# USB_to_SATA_bridge.net
KiCad netlist of a schematic drawn in Altium Designer
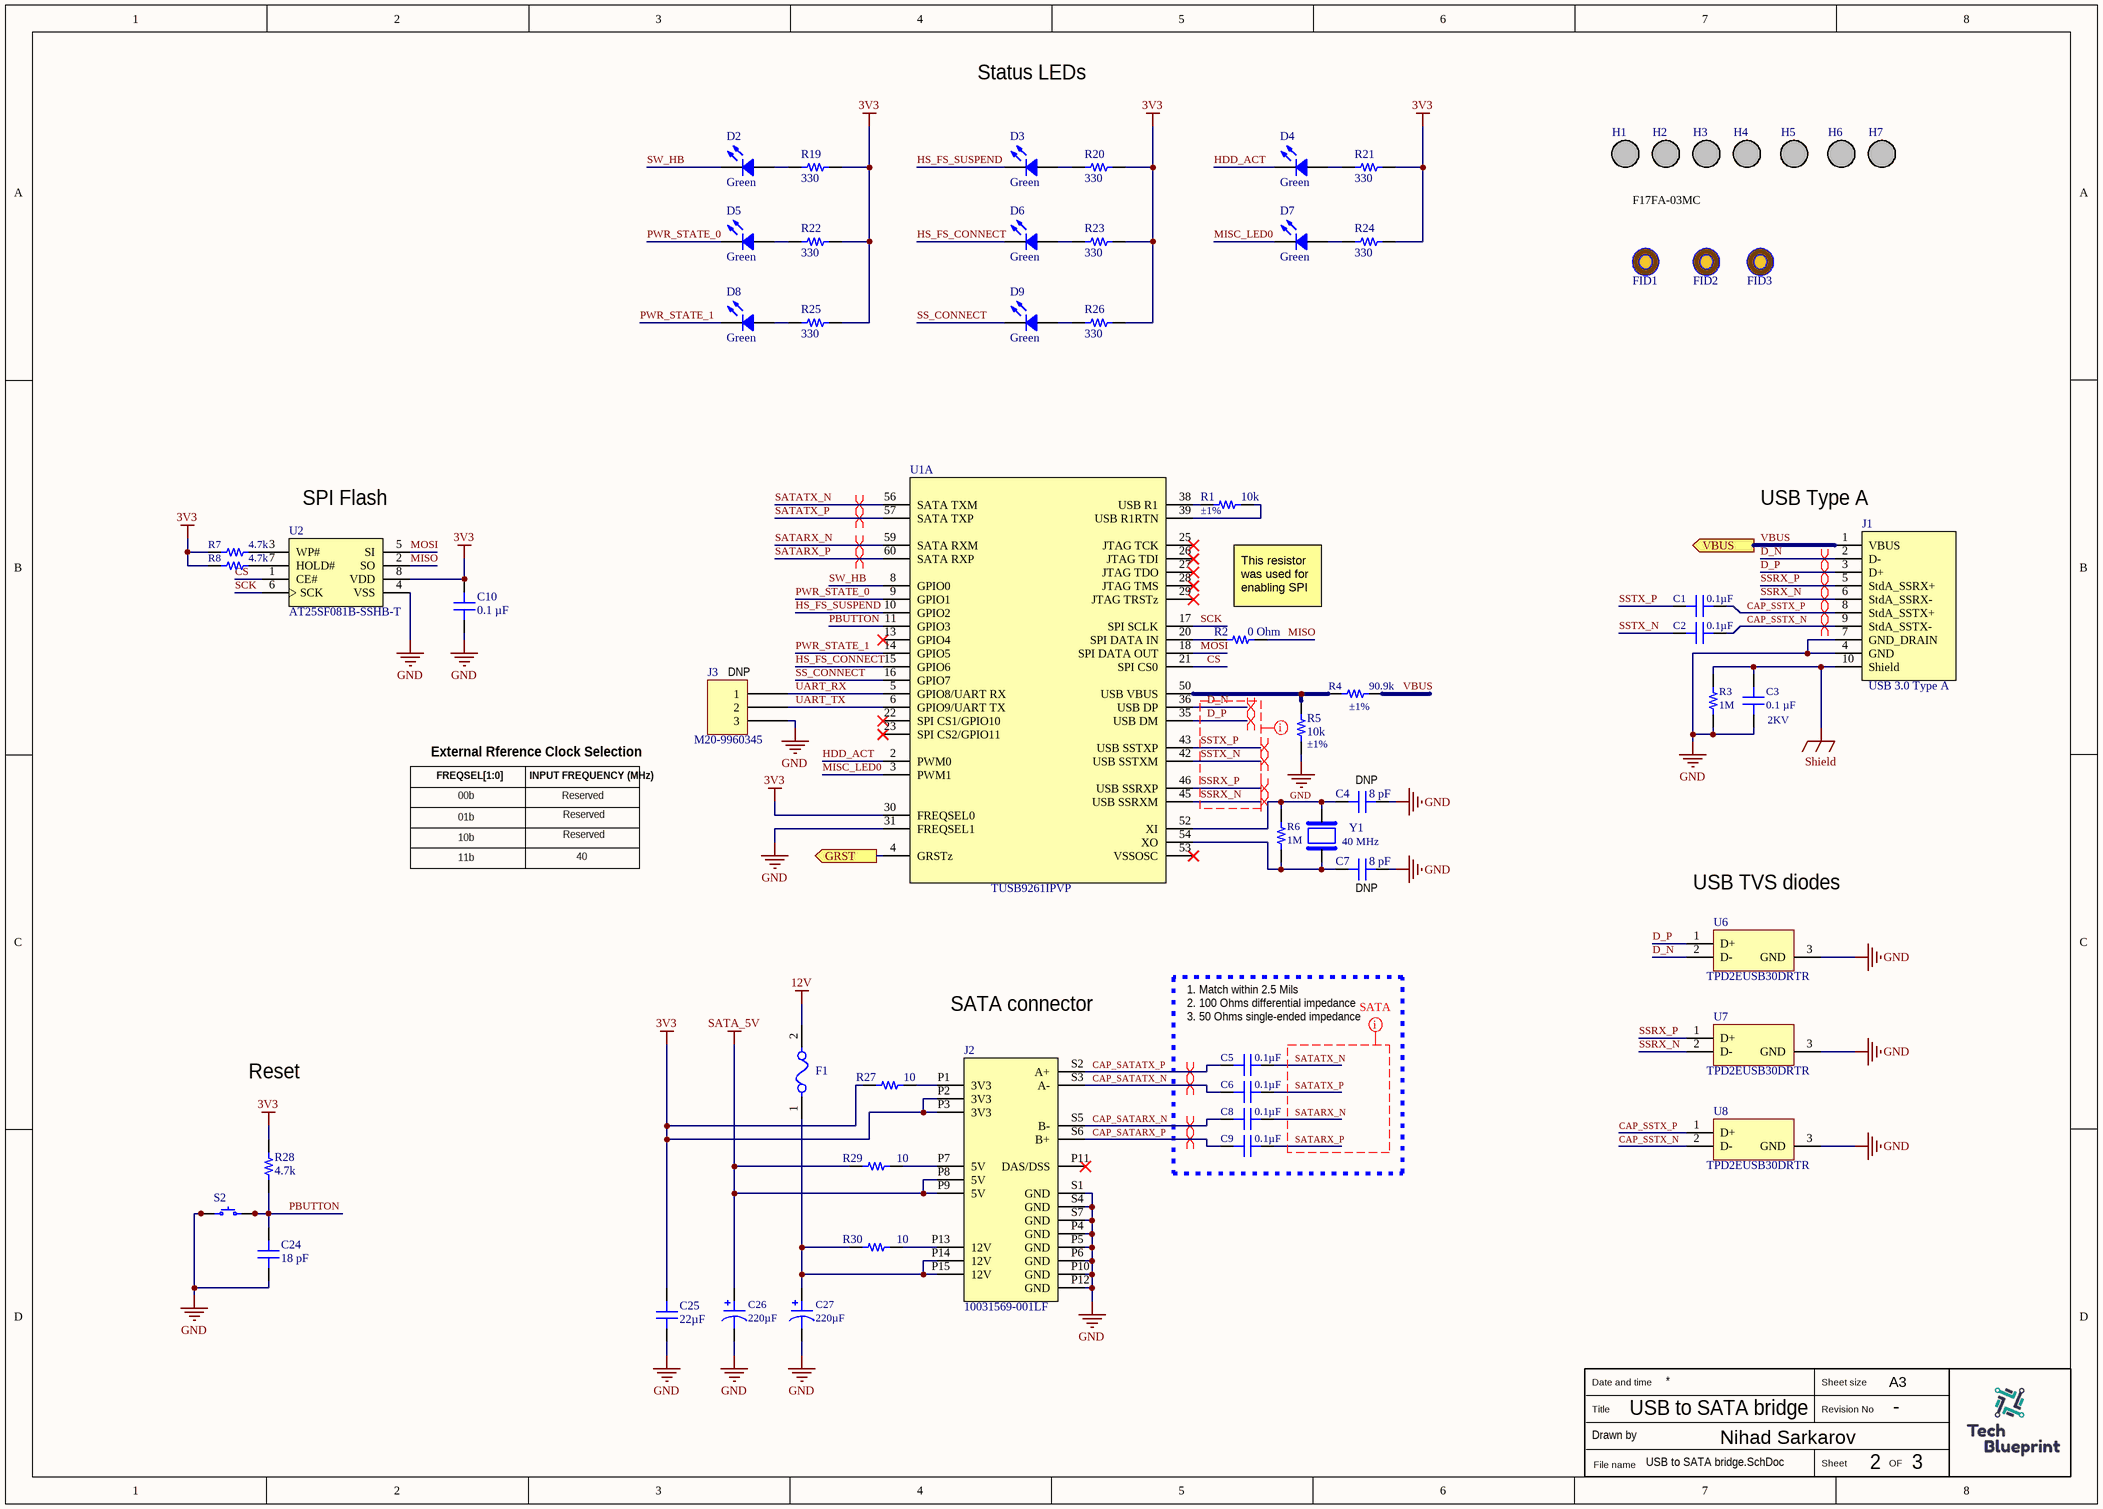
[diagram p0: USB to SATA bridge.SchDoc]

(export (version "E")
  (design (tool "Eeschema 10.0.6"))
  (components
    (comp (ref "C1")
      (value "0.1µF")
      (footprint "CAP 0402_1005")
      (description "CAP CER 0.1UF 16V X7R 0402")
      (fields
        (field (name "PART NUMBER") "0402YC104JAT4A")
        (field (name "CAPACITANCE") "0.1µF")
        (field (name "MANUFACTURER") "AVX Corporation")
      )
      (libsource (lib "Celestial Altium Library - altium_library") (part "Capacitor"))
    )
    (comp (ref "C2")
      (value "0.1µF")
      (footprint "CAP 0402_1005")
      (description "CAP CER 0.1UF 16V X7R 0402")
      (fields
        (field (name "PART NUMBER") "0402YC104JAT4A")
        (field (name "CAPACITANCE") "0.1µF")
        (field (name "MANUFACTURER") "AVX Corporation")
      )
      (libsource (lib "Celestial Altium Library - altium_library") (part "Capacitor"))
    )
    (comp (ref "C3")
      (value "0.1 µF")
      (footprint "MURATA GRM155 0402_1005")
      (description "CAP CER 0.1UF 100V X5R 0402")
      (fields
        (field (name "PART NUMBER") "GRM155R62A104ME14D")
        (field (name "CAPACITANCE") "0.1 µF")
        (field (name "MANUFACTURER") "Murata Electronics")
        (field (name "VOLTAGE - RATED") "2KV")
      )
      (libsource (lib "Celestial Altium Library - altium_library") (part "Capacitor"))
    )
    (comp (ref "C4")
      (value "8 pF")
      (footprint "MURATA GCM155 0402_1005")
      (description "CAP CER 8PF 50V C0G/NP0 0402")
      (fields
        (field (name "PART NUMBER") "GCM1555C1H8R0DA16D")
        (field (name "CAPACITANCE") "8 pF")
        (field (name "MANUFACTURER") "Murata Electronics")
      )
      (libsource (lib "Celestial Altium Library - altium_library") (part "Capacitor"))
    )
    (comp (ref "C5")
      (value "0.1µF")
      (footprint "CAP 0402_1005")
      (description "CAP CER 0.1UF 16V X7R 0402")
      (fields
        (field (name "PART NUMBER") "0402YC104JAT4A")
        (field (name "CAPACITANCE") "0.1µF")
        (field (name "MANUFACTURER") "AVX Corporation")
      )
      (libsource (lib "Celestial Altium Library - altium_library") (part "Capacitor"))
    )
    (comp (ref "C6")
      (value "0.1µF")
      (footprint "CAP 0402_1005")
      (description "CAP CER 0.1UF 16V X7R 0402")
      (fields
        (field (name "PART NUMBER") "0402YC104JAT4A")
        (field (name "CAPACITANCE") "0.1µF")
        (field (name "MANUFACTURER") "AVX Corporation")
      )
      (libsource (lib "Celestial Altium Library - altium_library") (part "Capacitor"))
    )
    (comp (ref "C7")
      (value "8 pF")
      (footprint "MURATA GCM155 0402_1005")
      (description "CAP CER 8PF 50V C0G/NP0 0402")
      (fields
        (field (name "PART NUMBER") "GCM1555C1H8R0DA16D")
        (field (name "CAPACITANCE") "8 pF")
        (field (name "MANUFACTURER") "Murata Electronics")
      )
      (libsource (lib "Celestial Altium Library - altium_library") (part "Capacitor"))
    )
    (comp (ref "C8")
      (value "0.1µF")
      (footprint "CAP 0402_1005")
      (description "CAP CER 0.1UF 16V X7R 0402")
      (fields
        (field (name "PART NUMBER") "0402YC104JAT4A")
        (field (name "CAPACITANCE") "0.1µF")
        (field (name "MANUFACTURER") "AVX Corporation")
      )
      (libsource (lib "Celestial Altium Library - altium_library") (part "Capacitor"))
    )
    (comp (ref "C9")
      (value "0.1µF")
      (footprint "CAP 0402_1005")
      (description "CAP CER 0.1UF 16V X7R 0402")
      (fields
        (field (name "PART NUMBER") "0402YC104JAT4A")
        (field (name "CAPACITANCE") "0.1µF")
        (field (name "MANUFACTURER") "AVX Corporation")
      )
      (libsource (lib "Celestial Altium Library - altium_library") (part "Capacitor"))
    )
    (comp (ref "C10")
      (value "0.1 µF")
      (footprint "CAP 0603_1608")
      (description "CAP CER 0.1UF 50V X7R 0603")
      (fields
        (field (name "PART NUMBER") "CL10B104KB85PND")
        (field (name "CAPACITANCE") "0.1 µF")
        (field (name "MANUFACTURER") "Samsung Electro-Mechanics")
      )
      (libsource (lib "Celestial Altium Library - altium_library") (part "Capacitor"))
    )
    (comp (ref "C24")
      (value "18 pF")
      (footprint "CAP 0402_1005")
      (description "CAP CER 18PF 50V C0G 0402")
      (fields
        (field (name "PART NUMBER") "CGA2B2C0G1H180J050BA")
        (field (name "CAPACITANCE") "18 pF")
        (field (name "MANUFACTURER") "TDK Corporation")
      )
      (libsource (lib "Celestial Altium Library - altium_library") (part "Capacitor"))
    )
    (comp (ref "C25")
      (value "22µF")
      (footprint "CAP 1206_3216 - 1.8MM")
      (description "CAP CER 22UF 16V X5R 1206")
      (fields
        (field (name "PART NUMBER") "1206YD226KAT2A")
        (field (name "CAPACITANCE") "22µF")
        (field (name "MANUFACTURER") "AVX Corporation")
      )
      (libsource (lib "Celestial Altium Library - altium_library") (part "Capacitor"))
    )
    (comp (ref "C26")
      (value "220µF")
      (footprint "CAP ALSMD 8.3MM H10.5MM")
      (description "CAP ALUM 220UF 20% 25V SMD")
      (fields (field (name "PART NUMBER") "UUR1E221MNL6GS") (field (name "MANUFACTURER") "Nichicon"))
      (libsource (lib "Celestial Altium Library - altium_library") (part "Polarised Capacitor"))
    )
    (comp (ref "C27")
      (value "220µF")
      (footprint "CAP ALSMD 8.3MM H10.5MM")
      (description "CAP ALUM 220UF 20% 25V SMD")
      (fields (field (name "PART NUMBER") "UUR1E221MNL6GS") (field (name "MANUFACTURER") "Nichicon"))
      (libsource (lib "Celestial Altium Library - altium_library") (part "Polarised Capacitor"))
    )
    (comp (ref "D2")
      (value "Green")
      (footprint "LED 0805_2012 GREEN")
      (description "0805 LED RED 570NM DOMINANT, 565")
      (fields
        (field (name "PART NUMBER") "QBLP631-YG1-2943")
        (field (name "MANUFACTURER") "QT Brightek (QTB)")
      )
      (libsource (lib "Celestial Altium Library - altium_library") (part "LED"))
    )
    (comp (ref "D3")
      (value "Green")
      (footprint "LED 0805_2012 GREEN")
      (description "0805 LED RED 570NM DOMINANT, 565")
      (fields
        (field (name "PART NUMBER") "QBLP631-YG1-2943")
        (field (name "MANUFACTURER") "QT Brightek (QTB)")
      )
      (libsource (lib "Celestial Altium Library - altium_library") (part "LED"))
    )
    (comp (ref "D4")
      (value "Green")
      (footprint "LED 0805_2012 GREEN")
      (description "0805 LED RED 570NM DOMINANT, 565")
      (fields
        (field (name "PART NUMBER") "QBLP631-YG1-2943")
        (field (name "MANUFACTURER") "QT Brightek (QTB)")
      )
      (libsource (lib "Celestial Altium Library - altium_library") (part "LED"))
    )
    (comp (ref "D5")
      (value "Green")
      (footprint "LED 0805_2012 GREEN")
      (description "0805 LED RED 570NM DOMINANT, 565")
      (fields
        (field (name "PART NUMBER") "QBLP631-YG1-2943")
        (field (name "MANUFACTURER") "QT Brightek (QTB)")
      )
      (libsource (lib "Celestial Altium Library - altium_library") (part "LED"))
    )
    (comp (ref "D6")
      (value "Green")
      (footprint "LED 0805_2012 GREEN")
      (description "0805 LED RED 570NM DOMINANT, 565")
      (fields
        (field (name "PART NUMBER") "QBLP631-YG1-2943")
        (field (name "MANUFACTURER") "QT Brightek (QTB)")
      )
      (libsource (lib "Celestial Altium Library - altium_library") (part "LED"))
    )
    (comp (ref "D7")
      (value "Green")
      (footprint "LED 0805_2012 GREEN")
      (description "0805 LED RED 570NM DOMINANT, 565")
      (fields
        (field (name "PART NUMBER") "QBLP631-YG1-2943")
        (field (name "MANUFACTURER") "QT Brightek (QTB)")
      )
      (libsource (lib "Celestial Altium Library - altium_library") (part "LED"))
    )
    (comp (ref "D8")
      (value "Green")
      (footprint "LED 0805_2012 GREEN")
      (description "0805 LED RED 570NM DOMINANT, 565")
      (fields
        (field (name "PART NUMBER") "QBLP631-YG1-2943")
        (field (name "MANUFACTURER") "QT Brightek (QTB)")
      )
      (libsource (lib "Celestial Altium Library - altium_library") (part "LED"))
    )
    (comp (ref "D9")
      (value "Green")
      (footprint "LED 0805_2012 GREEN")
      (description "0805 LED RED 570NM DOMINANT, 565")
      (fields
        (field (name "PART NUMBER") "QBLP631-YG1-2943")
        (field (name "MANUFACTURER") "QT Brightek (QTB)")
      )
      (libsource (lib "Celestial Altium Library - altium_library") (part "LED"))
    )
    (comp (ref "F1")
      (value "MINISMDC150F/24-2")
      (footprint "FP-MINISMDC150F-MFG")
      (description "PTC RESET FUSE 24V 1.5A 1812")
      (fields
        (field (name "MANUFACTURER") "Littelfuse")
        (field (name "OCTOPART") "https://octopart.com/minismdc150f%2F24-2-littelfuse-74215024")
      )
      (libsource (lib "Altium Content Vault") (part "5bcf9b9f640e542cf0359d10258e979"))
    )
    (comp (ref "FID1")
      (value "FID_040")
      (footprint "FID_040")
      (description "Fiducial with various available footprints")
      (libsource (lib "nRF52-Intro") (part "FIDUCIAL"))
    )
    (comp (ref "FID2")
      (value "FID_040")
      (footprint "FID_040")
      (description "Fiducial with various available footprints")
      (libsource (lib "nRF52-Intro") (part "FIDUCIAL"))
    )
    (comp (ref "FID3")
      (value "FID_040")
      (footprint "FID_040")
      (description "Fiducial with various available footprints")
      (libsource (lib "nRF52-Intro") (part "FIDUCIAL"))
    )
    (comp (ref "H1") (value "Hole") (footprint "Hole") (libsource (lib "USB to SATA") (part "Hole")))
    (comp (ref "H2") (value "Hole") (footprint "Hole") (libsource (lib "USB to SATA") (part "Hole")))
    (comp (ref "H3") (value "Hole") (footprint "Hole") (libsource (lib "USB to SATA") (part "Hole")))
    (comp (ref "H4")
      (value "Mounting hole")
      (footprint "Mounting hole")
      (libsource (lib "USB to SATA") (part "Mounting hole"))
    )
    (comp (ref "H5")
      (value "Mounting hole")
      (footprint "Mounting hole")
      (libsource (lib "USB to SATA") (part "Mounting hole"))
    )
    (comp (ref "H6")
      (value "Mounting hole")
      (footprint "Mounting hole")
      (libsource (lib "USB to SATA") (part "Mounting hole"))
    )
    (comp (ref "H7")
      (value "Mounting hole")
      (footprint "Mounting hole")
      (libsource (lib "USB to SATA") (part "Mounting hole"))
    )
    (comp (ref "J1")
      (value "USB 3.0 Type A")
      (footprint "USB 3.0 Type A")
      (description "USB 3.0 Type A male connector")
      (libsource (lib "USB to SATA") (part "USB 3.0 Type A"))
    )
    (comp (ref "J2")
      (value "10031569-001LF")
      (footprint "AMPHENOL_10031569-001LF")
      (fields (field (name "MF") "{'manufacturer': u'Amphenol ICC'}"))
      (libsource (lib "USB to SATA") (part "10031569-001LF"))
    )
    (comp (ref "J3")
      (value "M20-9960345")
      (footprint "HARWIN M20-9960345")
      (description "CONN HEADER R/A 3POS 2.54MM")
      (fields (field (name "MANUFACTURER") "Harwin Inc."))
      (libsource (lib "Celestial Altium Library - altium_library") (part "3 Pin"))
    )
    (comp (ref "R1")
      (value "10k")
      (footprint "YAGEO RES 0402_1005")
      (description "RES 10K OHM 1% 1/5W 0402")
      (fields
        (field (name "PART NUMBER") "SR0402FR-7T10KL")
        (field (name "MANUFACTURER") "Yageo")
        (field (name "TOLERANCE") "±1%")
      )
      (libsource (lib "Celestial Altium Library - altium_library") (part "Resistor"))
    )
    (comp (ref "R2")
      (value "0 Ohm")
      (footprint "RES 0603_1608")
      (description "RCS0603 0R0 ET6 E3")
      (fields (field (name "PART NUMBER") "RCS06030000Z0EC") (field (name "MANUFACTURER") "Vishay Dale"))
      (libsource (lib "Celestial Altium Library - altium_library") (part "Resistor"))
    )
    (comp (ref "R3")
      (value "1M")
      (footprint "RES 0603_1608")
      (description "RES 1M OHM 5% 1/10W 0603")
      (fields
        (field (name "PART NUMBER") "RMCF0603JT1M00")
        (field (name "MANUFACTURER") "Stackpole Electronics Inc")
      )
      (libsource (lib "Celestial Altium Library - altium_library") (part "Resistor"))
    )
    (comp (ref "R4")
      (value "90.9k")
      (footprint "RES 0603_1608")
      (description "RES SMD 90.9K OHM 1% 1/8W 0603")
      (fields
        (field (name "PART NUMBER") "MCT06030C9092FP500")
        (field (name "MANUFACTURER") "Vishay Beyschlag")
        (field (name "TOLERANCE") "±1%")
      )
      (libsource (lib "Celestial Altium Library - altium_library") (part "Resistor"))
    )
    (comp (ref "R5")
      (value "10k")
      (footprint "YAGEO RES 0603_1608")
      (description "RES SMD 10K OHM 1% 1/10W 0603")
      (fields
        (field (name "PART NUMBER") "RT0603FRE0710KL")
        (field (name "MANUFACTURER") "Yageo")
        (field (name "TOLERANCE") "±1%")
      )
      (libsource (lib "Celestial Altium Library - altium_library") (part "Resistor"))
    )
    (comp (ref "R6")
      (value "1M")
      (footprint "YAGEO RES 0402_1005")
      (description "RES SMD 1M OHM 5% 1/16W 0402")
      (fields (field (name "PART NUMBER") "AC0402JR-071ML") (field (name "MANUFACTURER") "Yageo"))
      (libsource (lib "Celestial Altium Library - altium_library") (part "Resistor"))
    )
    (comp (ref "R7")
      (value "4.7k")
      (footprint "RES 0603_1608")
      (description "RES 4.7K OHM 5% 1/10W 0603")
      (fields
        (field (name "PART NUMBER") "RMCF0603JT4K70")
        (field (name "MANUFACTURER") "Stackpole Electronics Inc")
      )
      (libsource (lib "Celestial Altium Library - altium_library") (part "Resistor"))
    )
    (comp (ref "R8")
      (value "4.7k")
      (footprint "RES 0603_1608")
      (description "RES 4.7K OHM 5% 1/10W 0603")
      (fields
        (field (name "PART NUMBER") "RMCF0603JT4K70")
        (field (name "MANUFACTURER") "Stackpole Electronics Inc")
      )
      (libsource (lib "Celestial Altium Library - altium_library") (part "Resistor"))
    )
    (comp (ref "R19")
      (value "330")
      (footprint "YAGEO RES 0402_1005")
      (description "RES SMD 330 OHM 5% 1/16W 0402")
      (fields (field (name "PART NUMBER") "AC0402JR-07330RL") (field (name "MANUFACTURER") "Yageo"))
      (libsource (lib "Celestial Altium Library - altium_library") (part "Resistor"))
    )
    (comp (ref "R20")
      (value "330")
      (footprint "YAGEO RES 0402_1005")
      (description "RES SMD 330 OHM 5% 1/16W 0402")
      (fields (field (name "PART NUMBER") "AC0402JR-07330RL") (field (name "MANUFACTURER") "Yageo"))
      (libsource (lib "Celestial Altium Library - altium_library") (part "Resistor"))
    )
    (comp (ref "R21")
      (value "330")
      (footprint "YAGEO RES 0402_1005")
      (description "RES SMD 330 OHM 5% 1/16W 0402")
      (fields (field (name "PART NUMBER") "AC0402JR-07330RL") (field (name "MANUFACTURER") "Yageo"))
      (libsource (lib "Celestial Altium Library - altium_library") (part "Resistor"))
    )
    (comp (ref "R22")
      (value "330")
      (footprint "YAGEO RES 0402_1005")
      (description "RES SMD 330 OHM 5% 1/16W 0402")
      (fields (field (name "PART NUMBER") "AC0402JR-07330RL") (field (name "MANUFACTURER") "Yageo"))
      (libsource (lib "Celestial Altium Library - altium_library") (part "Resistor"))
    )
    (comp (ref "R23")
      (value "330")
      (footprint "YAGEO RES 0402_1005")
      (description "RES SMD 330 OHM 5% 1/16W 0402")
      (fields (field (name "PART NUMBER") "AC0402JR-07330RL") (field (name "MANUFACTURER") "Yageo"))
      (libsource (lib "Celestial Altium Library - altium_library") (part "Resistor"))
    )
    (comp (ref "R24")
      (value "330")
      (footprint "YAGEO RES 0402_1005")
      (description "RES SMD 330 OHM 5% 1/16W 0402")
      (fields (field (name "PART NUMBER") "AC0402JR-07330RL") (field (name "MANUFACTURER") "Yageo"))
      (libsource (lib "Celestial Altium Library - altium_library") (part "Resistor"))
    )
    (comp (ref "R25")
      (value "330")
      (footprint "YAGEO RES 0402_1005")
      (description "RES SMD 330 OHM 5% 1/16W 0402")
      (fields (field (name "PART NUMBER") "AC0402JR-07330RL") (field (name "MANUFACTURER") "Yageo"))
      (libsource (lib "Celestial Altium Library - altium_library") (part "Resistor"))
    )
    (comp (ref "R26")
      (value "330")
      (footprint "YAGEO RES 0402_1005")
      (description "RES SMD 330 OHM 5% 1/16W 0402")
      (fields (field (name "PART NUMBER") "AC0402JR-07330RL") (field (name "MANUFACTURER") "Yageo"))
      (libsource (lib "Celestial Altium Library - altium_library") (part "Resistor"))
    )
    (comp (ref "R27")
      (value "10")
      (footprint "RES 1206_3216")
      (description "RCC1206 200 10R 5% ET1 E3")
      (fields (field (name "PART NUMBER") "RCC120610R0JNEA") (field (name "MANUFACTURER") "Vishay Dale"))
      (libsource (lib "Celestial Altium Library - altium_library") (part "Resistor"))
    )
    (comp (ref "R28")
      (value "4.7k")
      (footprint "YAGEO RES 0402_1005")
      (description "RES SMD 4.7K OHM 5% 1/16W 0402")
      (fields (field (name "PART NUMBER") "AC0402JR-074K7L") (field (name "MANUFACTURER") "Yageo"))
      (libsource (lib "Celestial Altium Library - altium_library") (part "Resistor"))
    )
    (comp (ref "R29")
      (value "10")
      (footprint "RES 1206_3216")
      (description "RCC1206 200 10R 5% ET1 E3")
      (fields (field (name "PART NUMBER") "RCC120610R0JNEA") (field (name "MANUFACTURER") "Vishay Dale"))
      (libsource (lib "Celestial Altium Library - altium_library") (part "Resistor"))
    )
    (comp (ref "R30")
      (value "10")
      (footprint "RES 1206_3216")
      (description "RCC1206 200 10R 5% ET1 E3")
      (fields (field (name "PART NUMBER") "RCC120610R0JNEA") (field (name "MANUFACTURER") "Vishay Dale"))
      (libsource (lib "Celestial Altium Library - altium_library") (part "Resistor"))
    )
    (comp (ref "S2")
      (value "PTS645SM43SMTR92 LFS")
      (footprint "C&K PTS645")
      (description "SWITCH TACTILE SPST-NO 0.05A 12V")
      (fields (field (name "MANUFACTURER") "C&K"))
      (libsource (lib "Celestial Altium Library - altium_library") (part "SPST-NO 4 PIN"))
    )
    (comp (ref "U1")
      (value "TUSB9261IPVP")
      (footprint "FP-PVP0064A-IPC_A")
      (description "HDD, CD, DVD Drive Interface 64-HTQFP (7x7)")
      (fields
        (field (name "MANUFACTURER") "Texas Instruments")
        (field (name "DIGIKEY PART NUMBER") "296-35545-ND")
      )
      (libsource (lib "USB to SATA") (part "TUSB9261IPVP"))
    )
    (comp (ref "U2")
      (value "AT25SF081B-SSHB-T")
      (footprint "SST25VF016B-75-4I-S2AF-T:SOIC127P790X216-8N")
      (description "FLASH - NOR Memory IC 8Mbit SPI - Quad I/O 108 MHz 8-SOIC")
      (fields
        (field (name "MF") "{'manufacturer': u'Microchip Technology'}")
        (field (name "MP") "SST25VF016B-75-4I-S2AF-T")
      )
      (libsource (lib "USB to SATA") (part "SST25VF016B-75-4I-S2AF-T"))
    )
    (comp (ref "U6")
      (value "TPD2EUSB30DRTR")
      (footprint "DRT0003A")
      (fields (field (name "MANUFACTURER") "Texas Instruments"))
      (libsource (lib "Altium Content Vault") (part "TI-TPD2EUSB30-SOT_DRT-3"))
    )
    (comp (ref "U7")
      (value "TPD2EUSB30DRTR")
      (footprint "DRT0003A")
      (fields (field (name "MANUFACTURER") "Texas Instruments"))
      (libsource (lib "Altium Content Vault") (part "TI-TPD2EUSB30-SOT_DRT-3"))
    )
    (comp (ref "U8")
      (value "TPD2EUSB30DRTR")
      (footprint "DRT0003A")
      (fields (field (name "MANUFACTURER") "Texas Instruments"))
      (libsource (lib "Altium Content Vault") (part "TI-TPD2EUSB30-SOT_DRT-3"))
    )
    (comp (ref "Y1")
      (value "SXT22412AA07-40.000M")
      (footprint "XTAL_SXT22412AA16-40.000MT")
      (description "40 MHz ±50ppm Crystal 12pF 50 Ohms 4-SMD, No Lead")
      (fields (field (name "MF") "Suntsu Electronics, Inc") (field (name "FREQUENCY") "40 MHz"))
      (libsource (lib "USB to SATA") (part "SXT22412AA07-40.000M"))
    )
  )
  (nets
    (net (code "1") (name "/CAP_SATARX_N") (class "Default")
      (node (ref "C8") (pin "1") (pinfunction "1_1") (pintype "passive"))
      (node (ref "J2") (pin "S5") (pinfunction "B-_S5") (pintype "passive"))
    )
    (net (code "2") (name "/CAP_SATARX_P") (class "Default")
      (node (ref "C9") (pin "1") (pinfunction "1_1") (pintype "passive"))
      (node (ref "J2") (pin "S6") (pinfunction "B+_S6") (pintype "passive"))
    )
    (net (code "3") (name "/CAP_SATATX_N") (class "Default")
      (node (ref "C6") (pin "1") (pinfunction "1_1") (pintype "passive"))
      (node (ref "J2") (pin "S3") (pinfunction "A-_S3") (pintype "passive"))
    )
    (net (code "4") (name "/CAP_SATATX_P") (class "Default")
      (node (ref "C5") (pin "1") (pinfunction "1_1") (pintype "passive"))
      (node (ref "J2") (pin "S2") (pinfunction "A+_S2") (pintype "passive"))
    )
    (net (code "5") (name "/CAP_SSTX_N") (class "Default")
      (node (ref "C2") (pin "2") (pinfunction "2_2") (pintype "passive"))
      (node (ref "J1") (pin "9") (pinfunction "StdA_SSTX-_9") (pintype "passive"))
      (node (ref "U8") (pin "2") (pinfunction "D-_2") (pintype "passive"))
    )
    (net (code "6") (name "/CAP_SSTX_P") (class "Default")
      (node (ref "C1") (pin "2") (pinfunction "2_2") (pintype "passive"))
      (node (ref "J1") (pin "8") (pinfunction "StdA_SSTX+_8") (pintype "passive"))
      (node (ref "U8") (pin "1") (pinfunction "D+_1") (pintype "passive"))
    )
    (net (code "7") (name "/CS") (class "Default")
      (node (ref "U1") (pin "21") (pinfunction "SPI_CS0_21") (pintype "passive"))
      (node (ref "U2") (pin "1") (pinfunction "CE#_1") (pintype "passive"))
    )
    (net (code "8") (name "/D_N") (class "Default")
      (node (ref "J1") (pin "2") (pinfunction "D-_2") (pintype "passive"))
      (node (ref "U1") (pin "36") (pinfunction "USB_DP_36") (pintype "passive"))
      (node (ref "U6") (pin "2") (pinfunction "D-_2") (pintype "passive"))
    )
    (net (code "9") (name "/D_P") (class "Default")
      (node (ref "J1") (pin "3") (pinfunction "D+_3") (pintype "passive"))
      (node (ref "U1") (pin "35") (pinfunction "USB_DM_35") (pintype "passive"))
      (node (ref "U6") (pin "1") (pinfunction "D+_1") (pintype "passive"))
    )
    (net (code "10") (name "/GRST") (class "Default")
      (node (ref "U1") (pin "4") (pinfunction "GRSTz_4") (pintype "passive"))
    )
    (net (code "11") (name "/HDD_ACT") (class "Default")
      (node (ref "D4") (pin "2") (pinfunction "2_2") (pintype "passive"))
      (node (ref "U1") (pin "2") (pinfunction "PWM0_2") (pintype "passive"))
    )
    (net (code "12") (name "/HS_FS_CONNECT") (class "Default")
      (node (ref "D6") (pin "2") (pinfunction "2_2") (pintype "passive"))
      (node (ref "U1") (pin "15") (pinfunction "GPIO6_15") (pintype "passive"))
    )
    (net (code "13") (name "/HS_FS_SUSPEND") (class "Default")
      (node (ref "D3") (pin "2") (pinfunction "2_2") (pintype "passive"))
      (node (ref "U1") (pin "10") (pinfunction "GPIO2_10") (pintype "passive"))
    )
    (net (code "14") (name "/MISC_LED0") (class "Default")
      (node (ref "D7") (pin "2") (pinfunction "2_2") (pintype "passive"))
      (node (ref "U1") (pin "3") (pinfunction "PWM1_3") (pintype "passive"))
    )
    (net (code "15") (name "/MISO") (class "Default")
      (node (ref "R2") (pin "2") (pinfunction "2_2") (pintype "passive"))
      (node (ref "U2") (pin "2") (pinfunction "SO_2") (pintype "passive"))
    )
    (net (code "16") (name "/MOSI") (class "Default")
      (node (ref "U1") (pin "18") (pinfunction "SPI_DATA_OUT_18") (pintype "passive"))
      (node (ref "U2") (pin "5") (pinfunction "SI_5") (pintype "passive"))
    )
    (net (code "17") (name "/PBUTTON") (class "Default")
      (node (ref "C24") (pin "2") (pinfunction "2_2") (pintype "passive"))
      (node (ref "R28") (pin "1") (pinfunction "1_1") (pintype "passive"))
      (node (ref "S2") (pin "3") (pinfunction "3_3") (pintype "passive"))
      (node (ref "S2") (pin "4") (pinfunction "4_4") (pintype "passive"))
      (node (ref "U1") (pin "11") (pinfunction "GPIO3_11") (pintype "passive"))
    )
    (net (code "18") (name "/PWR_STATE_0") (class "Default")
      (node (ref "D5") (pin "2") (pinfunction "2_2") (pintype "passive"))
      (node (ref "U1") (pin "9") (pinfunction "GPIO1_9") (pintype "passive"))
    )
    (net (code "19") (name "/PWR_STATE_1") (class "Default")
      (node (ref "D8") (pin "2") (pinfunction "2_2") (pintype "passive"))
      (node (ref "U1") (pin "14") (pinfunction "GPIO5_14") (pintype "passive"))
    )
    (net (code "20") (name "/SATARX_N") (class "Default")
      (node (ref "C8") (pin "2") (pinfunction "2_2") (pintype "passive"))
      (node (ref "U1") (pin "59") (pinfunction "SATA_RXM_59") (pintype "passive"))
    )
    (net (code "21") (name "/SATARX_P") (class "Default")
      (node (ref "C9") (pin "2") (pinfunction "2_2") (pintype "passive"))
      (node (ref "U1") (pin "60") (pinfunction "SATA_RXP_60") (pintype "passive"))
    )
    (net (code "22") (name "/SATATX_N") (class "Default")
      (node (ref "C5") (pin "2") (pinfunction "2_2") (pintype "passive"))
      (node (ref "U1") (pin "56") (pinfunction "SATA_TXM_56") (pintype "passive"))
    )
    (net (code "23") (name "/SATATX_P") (class "Default")
      (node (ref "C6") (pin "2") (pinfunction "2_2") (pintype "passive"))
      (node (ref "U1") (pin "57") (pinfunction "SATA_TXP_57") (pintype "passive"))
    )
    (net (code "24") (name "/SCK") (class "Default")
      (node (ref "U1") (pin "17") (pinfunction "SPI_SCLK_17") (pintype "passive"))
      (node (ref "U2") (pin "6") (pinfunction "SCK_6") (pintype "passive"))
    )
    (net (code "25") (name "/SSRX_N") (class "Default")
      (node (ref "J1") (pin "6") (pinfunction "StdA_SSRX-_6") (pintype "passive"))
      (node (ref "U1") (pin "45") (pinfunction "USB_SSRXM_45") (pintype "passive"))
      (node (ref "U7") (pin "2") (pinfunction "D-_2") (pintype "passive"))
    )
    (net (code "26") (name "/SSRX_P") (class "Default")
      (node (ref "J1") (pin "5") (pinfunction "StdA_SSRX+_5") (pintype "passive"))
      (node (ref "U1") (pin "46") (pinfunction "USB_SSRXP_46") (pintype "passive"))
      (node (ref "U7") (pin "1") (pinfunction "D+_1") (pintype "passive"))
    )
    (net (code "27") (name "/SSTX_N") (class "Default")
      (node (ref "C2") (pin "1") (pinfunction "1_1") (pintype "passive"))
      (node (ref "U1") (pin "42") (pinfunction "USB_SSTXM_42") (pintype "passive"))
    )
    (net (code "28") (name "/SSTX_P") (class "Default")
      (node (ref "C1") (pin "1") (pinfunction "1_1") (pintype "passive"))
      (node (ref "U1") (pin "43") (pinfunction "USB_SSTXP_43") (pintype "passive"))
    )
    (net (code "29") (name "/SS_CONNECT") (class "Default")
      (node (ref "D9") (pin "2") (pinfunction "2_2") (pintype "passive"))
      (node (ref "U1") (pin "16") (pinfunction "GPIO7_16") (pintype "passive"))
    )
    (net (code "30") (name "/SW_HB") (class "Default")
      (node (ref "D2") (pin "2") (pinfunction "2_2") (pintype "passive"))
      (node (ref "U1") (pin "8") (pinfunction "GPIO0_8") (pintype "passive"))
    )
    (net (code "31") (name "/UART_RX") (class "Default")
      (node (ref "J3") (pin "1") (pinfunction "1_1") (pintype "passive"))
      (node (ref "U1") (pin "5") (pinfunction "GPIO8/UART_RX_5") (pintype "passive"))
    )
    (net (code "32") (name "/UART_TX") (class "Default")
      (node (ref "J3") (pin "2") (pinfunction "2_2") (pintype "passive"))
      (node (ref "U1") (pin "6") (pinfunction "GPIO9/UART_TX_6") (pintype "passive"))
    )
    (net (code "33") (name "/VBUS") (class "Default")
      (node (ref "J1") (pin "1") (pinfunction "VBUS_1") (pintype "passive"))
      (node (ref "R4") (pin "2") (pinfunction "2_2") (pintype "passive"))
    )
    (net (code "34") (name "3V3") (class "Default")
      (node (ref "C10") (pin "2") (pinfunction "2_2") (pintype "passive"))
      (node (ref "C25") (pin "2") (pinfunction "2_2") (pintype "passive"))
      (node (ref "J2") (pin "P2") (pinfunction "3V3_P2") (pintype "passive"))
      (node (ref "J2") (pin "P3") (pinfunction "3V3_P3") (pintype "passive"))
      (node (ref "R19") (pin "2") (pinfunction "2_2") (pintype "passive"))
      (node (ref "R20") (pin "2") (pinfunction "2_2") (pintype "passive"))
      (node (ref "R21") (pin "2") (pinfunction "2_2") (pintype "passive"))
      (node (ref "R22") (pin "2") (pinfunction "2_2") (pintype "passive"))
      (node (ref "R23") (pin "2") (pinfunction "2_2") (pintype "passive"))
      (node (ref "R24") (pin "2") (pinfunction "2_2") (pintype "passive"))
      (node (ref "R25") (pin "2") (pinfunction "2_2") (pintype "passive"))
      (node (ref "R26") (pin "2") (pinfunction "2_2") (pintype "passive"))
      (node (ref "R27") (pin "1") (pinfunction "1_1") (pintype "passive"))
      (node (ref "R28") (pin "2") (pinfunction "2_2") (pintype "passive"))
      (node (ref "R7") (pin "1") (pinfunction "1_1") (pintype "passive"))
      (node (ref "R8") (pin "1") (pinfunction "1_1") (pintype "passive"))
      (node (ref "U1") (pin "30") (pinfunction "FREQSEL0_30") (pintype "passive"))
      (node (ref "U2") (pin "8") (pinfunction "VDD_8") (pintype "power_in"))
    )
    (net (code "35") (name "12V") (class "Default")
      (node (ref "F1") (pin "2") (pinfunction "2_2") (pintype "passive"))
    )
    (net (code "36") (name "GND") (class "Default")
      (node (ref "C10") (pin "1") (pinfunction "1_1") (pintype "passive"))
      (node (ref "C24") (pin "1") (pinfunction "1_1") (pintype "passive"))
      (node (ref "C25") (pin "1") (pinfunction "1_1") (pintype "passive"))
      (node (ref "C26") (pin "2") (pinfunction "2_2") (pintype "passive"))
      (node (ref "C27") (pin "2") (pinfunction "2_2") (pintype "passive"))
      (node (ref "C3") (pin "1") (pinfunction "1_1") (pintype "passive"))
      (node (ref "C4") (pin "2") (pinfunction "2_2") (pintype "passive"))
      (node (ref "C7") (pin "2") (pinfunction "2_2") (pintype "passive"))
      (node (ref "J1") (pin "4") (pinfunction "GND_4") (pintype "passive"))
      (node (ref "J1") (pin "7") (pinfunction "GND_DRAIN_7") (pintype "passive"))
      (node (ref "J2") (pin "P10") (pinfunction "GND_P10") (pintype "passive"))
      (node (ref "J2") (pin "P12") (pinfunction "GND_P12") (pintype "passive"))
      (node (ref "J2") (pin "P4") (pinfunction "GND_P4") (pintype "passive"))
      (node (ref "J2") (pin "P5") (pinfunction "GND_P5") (pintype "passive"))
      (node (ref "J2") (pin "P6") (pinfunction "GND_P6") (pintype "passive"))
      (node (ref "J2") (pin "S1") (pinfunction "GND_S1") (pintype "passive"))
      (node (ref "J2") (pin "S4") (pinfunction "GND_S4") (pintype "passive"))
      (node (ref "J2") (pin "S7") (pinfunction "GND_S7") (pintype "passive"))
      (node (ref "J3") (pin "3") (pinfunction "3_3") (pintype "passive"))
      (node (ref "R3") (pin "1") (pinfunction "1_1") (pintype "passive"))
      (node (ref "R5") (pin "1") (pinfunction "1_1") (pintype "passive"))
      (node (ref "S2") (pin "1") (pinfunction "1_1") (pintype "passive"))
      (node (ref "S2") (pin "2") (pinfunction "2_2") (pintype "passive"))
      (node (ref "U1") (pin "31") (pinfunction "FREQSEL1_31") (pintype "passive"))
      (node (ref "U2") (pin "4") (pinfunction "VSS_4") (pintype "power_in"))
      (node (ref "U6") (pin "3") (pinfunction "GND_3") (pintype "power_in"))
      (node (ref "U7") (pin "3") (pinfunction "GND_3") (pintype "power_in"))
      (node (ref "U8") (pin "3") (pinfunction "GND_3") (pintype "power_in"))
    )
    (net (code "37") (name "Net-(C27-Pad1)") (class "Default")
      (node (ref "C27") (pin "1") (pinfunction "1_1") (pintype "passive"))
      (node (ref "F1") (pin "1") (pinfunction "1_1") (pintype "passive"))
      (node (ref "J2") (pin "P14") (pinfunction "12V_P14") (pintype "passive"))
      (node (ref "J2") (pin "P15") (pinfunction "12V_P15") (pintype "passive"))
      (node (ref "R30") (pin "1") (pinfunction "1_1") (pintype "passive"))
    )
    (net (code "38") (name "Net-(D2-Pad1)") (class "Default")
      (node (ref "D2") (pin "1") (pinfunction "1_1") (pintype "passive"))
      (node (ref "R19") (pin "1") (pinfunction "1_1") (pintype "passive"))
    )
    (net (code "39") (name "Net-(D3-Pad1)") (class "Default")
      (node (ref "D3") (pin "1") (pinfunction "1_1") (pintype "passive"))
      (node (ref "R20") (pin "1") (pinfunction "1_1") (pintype "passive"))
    )
    (net (code "40") (name "Net-(D4-Pad1)") (class "Default")
      (node (ref "D4") (pin "1") (pinfunction "1_1") (pintype "passive"))
      (node (ref "R21") (pin "1") (pinfunction "1_1") (pintype "passive"))
    )
    (net (code "41") (name "Net-(D5-Pad1)") (class "Default")
      (node (ref "D5") (pin "1") (pinfunction "1_1") (pintype "passive"))
      (node (ref "R22") (pin "1") (pinfunction "1_1") (pintype "passive"))
    )
    (net (code "42") (name "Net-(D6-Pad1)") (class "Default")
      (node (ref "D6") (pin "1") (pinfunction "1_1") (pintype "passive"))
      (node (ref "R23") (pin "1") (pinfunction "1_1") (pintype "passive"))
    )
    (net (code "43") (name "Net-(D7-Pad1)") (class "Default")
      (node (ref "D7") (pin "1") (pinfunction "1_1") (pintype "passive"))
      (node (ref "R24") (pin "1") (pinfunction "1_1") (pintype "passive"))
    )
    (net (code "44") (name "Net-(D8-Pad1)") (class "Default")
      (node (ref "D8") (pin "1") (pinfunction "1_1") (pintype "passive"))
      (node (ref "R25") (pin "1") (pinfunction "1_1") (pintype "passive"))
    )
    (net (code "45") (name "Net-(D9-Pad1)") (class "Default")
      (node (ref "D9") (pin "1") (pinfunction "1_1") (pintype "passive"))
      (node (ref "R26") (pin "1") (pinfunction "1_1") (pintype "passive"))
    )
    (net (code "46") (name "Net-(J2-3V3-PadP1)") (class "Default")
      (node (ref "J2") (pin "P1") (pinfunction "3V3_P1") (pintype "passive"))
      (node (ref "R27") (pin "2") (pinfunction "2_2") (pintype "passive"))
    )
    (net (code "47") (name "Net-(J2-5V-PadP7)") (class "Default")
      (node (ref "J2") (pin "P7") (pinfunction "5V_P7") (pintype "passive"))
      (node (ref "R29") (pin "2") (pinfunction "2_2") (pintype "passive"))
    )
    (net (code "48") (name "Net-(J2-12V-PadP13)") (class "Default")
      (node (ref "J2") (pin "P13") (pinfunction "12V_P13") (pintype "passive"))
      (node (ref "R30") (pin "2") (pinfunction "2_2") (pintype "passive"))
    )
    (net (code "49") (name "Net-(U1A-SPI_DATA_IN)") (class "Default")
      (node (ref "R2") (pin "1") (pinfunction "1_1") (pintype "passive"))
      (node (ref "U1") (pin "20") (pinfunction "SPI_DATA_IN_20") (pintype "passive"))
    )
    (net (code "50") (name "Net-(U1A-USB_R1)") (class "Default")
      (node (ref "R1") (pin "1") (pinfunction "1_1") (pintype "passive"))
      (node (ref "U1") (pin "38") (pinfunction "USB_R1_38") (pintype "passive"))
    )
    (net (code "51") (name "Net-(U1A-USB_R1RTN)") (class "Default")
      (node (ref "R1") (pin "2") (pinfunction "2_2") (pintype "passive"))
      (node (ref "U1") (pin "39") (pinfunction "USB_R1RTN_39") (pintype "passive"))
    )
    (net (code "52") (name "Net-(U1A-USB_VBUS)") (class "Default")
      (node (ref "R4") (pin "1") (pinfunction "1_1") (pintype "passive"))
      (node (ref "R5") (pin "2") (pinfunction "2_2") (pintype "passive"))
      (node (ref "U1") (pin "50") (pinfunction "USB_VBUS_50") (pintype "passive"))
    )
    (net (code "53") (name "Net-(U1A-XI)") (class "Default")
      (node (ref "C4") (pin "1") (pinfunction "1_1") (pintype "passive"))
      (node (ref "R6") (pin "2") (pinfunction "2_2") (pintype "passive"))
      (node (ref "U1") (pin "52") (pinfunction "XI_52") (pintype "passive"))
      (node (ref "Y1") (pin "3") (pinfunction "3_3") (pintype "passive"))
    )
    (net (code "54") (name "Net-(U1A-XO)") (class "Default")
      (node (ref "C7") (pin "1") (pinfunction "1_1") (pintype "passive"))
      (node (ref "R6") (pin "1") (pinfunction "1_1") (pintype "passive"))
      (node (ref "U1") (pin "54") (pinfunction "XO_54") (pintype "passive"))
      (node (ref "Y1") (pin "1") (pinfunction "1_1") (pintype "passive"))
    )
    (net (code "55") (name "Net-(U2-HOLD#)") (class "Default")
      (node (ref "R8") (pin "2") (pinfunction "2_2") (pintype "passive"))
      (node (ref "U2") (pin "7") (pinfunction "HOLD#_7") (pintype "passive"))
    )
    (net (code "56") (name "Net-(U2-WP#)") (class "Default")
      (node (ref "R7") (pin "2") (pinfunction "2_2") (pintype "passive"))
      (node (ref "U2") (pin "3") (pinfunction "WP#_3") (pintype "passive"))
    )
    (net (code "57") (name "SATA_5V") (class "Default")
      (node (ref "C26") (pin "1") (pinfunction "1_1") (pintype "passive"))
      (node (ref "J2") (pin "P8") (pinfunction "5V_P8") (pintype "passive"))
      (node (ref "J2") (pin "P9") (pinfunction "5V_P9") (pintype "passive"))
      (node (ref "R29") (pin "1") (pinfunction "1_1") (pintype "passive"))
    )
    (net (code "58") (name "Shield") (class "Default")
      (node (ref "C3") (pin "2") (pinfunction "2_2") (pintype "passive"))
      (node (ref "J1") (pin "10") (pinfunction "Shield_10") (pintype "passive"))
      (node (ref "R3") (pin "2") (pinfunction "2_2") (pintype "passive"))
    )
    (net (code "59") (name "unconnected-(FID1-PadFID)") (class "Default")
      (node (ref "FID1") (pin "FID") (pinfunction "FID_FID") (pintype "input"))
    )
    (net (code "60") (name "unconnected-(FID2-PadFID)") (class "Default")
      (node (ref "FID2") (pin "FID") (pinfunction "FID_FID") (pintype "input"))
    )
    (net (code "61") (name "unconnected-(FID3-PadFID)") (class "Default")
      (node (ref "FID3") (pin "FID") (pinfunction "FID_FID") (pintype "input"))
    )
    (net (code "62") (name "unconnected-(J2-DAS{slash}DSS-PadP11)") (class "Default")
      (node (ref "J2") (pin "P11") (pinfunction "DAS/DSS_P11") (pintype "passive+no_connect"))
    )
    (net (code "63") (name "unconnected-(U1A-GPIO4-Pad13)") (class "Default")
      (node (ref "U1") (pin "13") (pinfunction "GPIO4_13") (pintype "passive+no_connect"))
    )
    (net (code "64") (name "unconnected-(U1A-JTAG_TCK-Pad25)") (class "Default")
      (node (ref "U1") (pin "25") (pinfunction "JTAG_TCK_25") (pintype "passive+no_connect"))
    )
    (net (code "65") (name "unconnected-(U1A-JTAG_TDI-Pad26)") (class "Default")
      (node (ref "U1") (pin "26") (pinfunction "JTAG_TDI_26") (pintype "passive+no_connect"))
    )
    (net (code "66") (name "unconnected-(U1A-JTAG_TDO-Pad27)") (class "Default")
      (node (ref "U1") (pin "27") (pinfunction "JTAG_TDO_27") (pintype "passive+no_connect"))
    )
    (net (code "67") (name "unconnected-(U1A-JTAG_TMS-Pad28)") (class "Default")
      (node (ref "U1") (pin "28") (pinfunction "JTAG_TMS_28") (pintype "passive+no_connect"))
    )
    (net (code "68") (name "unconnected-(U1A-JTAG_TRSTz-Pad29)") (class "Default")
      (node (ref "U1") (pin "29") (pinfunction "JTAG_TRSTz_29") (pintype "passive+no_connect"))
    )
    (net (code "69") (name "unconnected-(U1A-SPI_CS1{slash}GPIO10-Pad22)") (class "Default")
      (node (ref "U1") (pin "22") (pinfunction "SPI_CS1/GPIO10_22") (pintype "passive+no_connect"))
    )
    (net (code "70") (name "unconnected-(U1A-SPI_CS2{slash}GPIO11-Pad23)") (class "Default")
      (node (ref "U1") (pin "23") (pinfunction "SPI_CS2/GPIO11_23") (pintype "passive+no_connect"))
    )
    (net (code "71") (name "unconnected-(U1A-VSSOSC-Pad53)") (class "Default")
      (node (ref "U1") (pin "53") (pinfunction "VSSOSC_53") (pintype "passive+no_connect"))
    )
  )
)
